# Power.net
KiCad netlist of a schematic drawn in Altium Designer
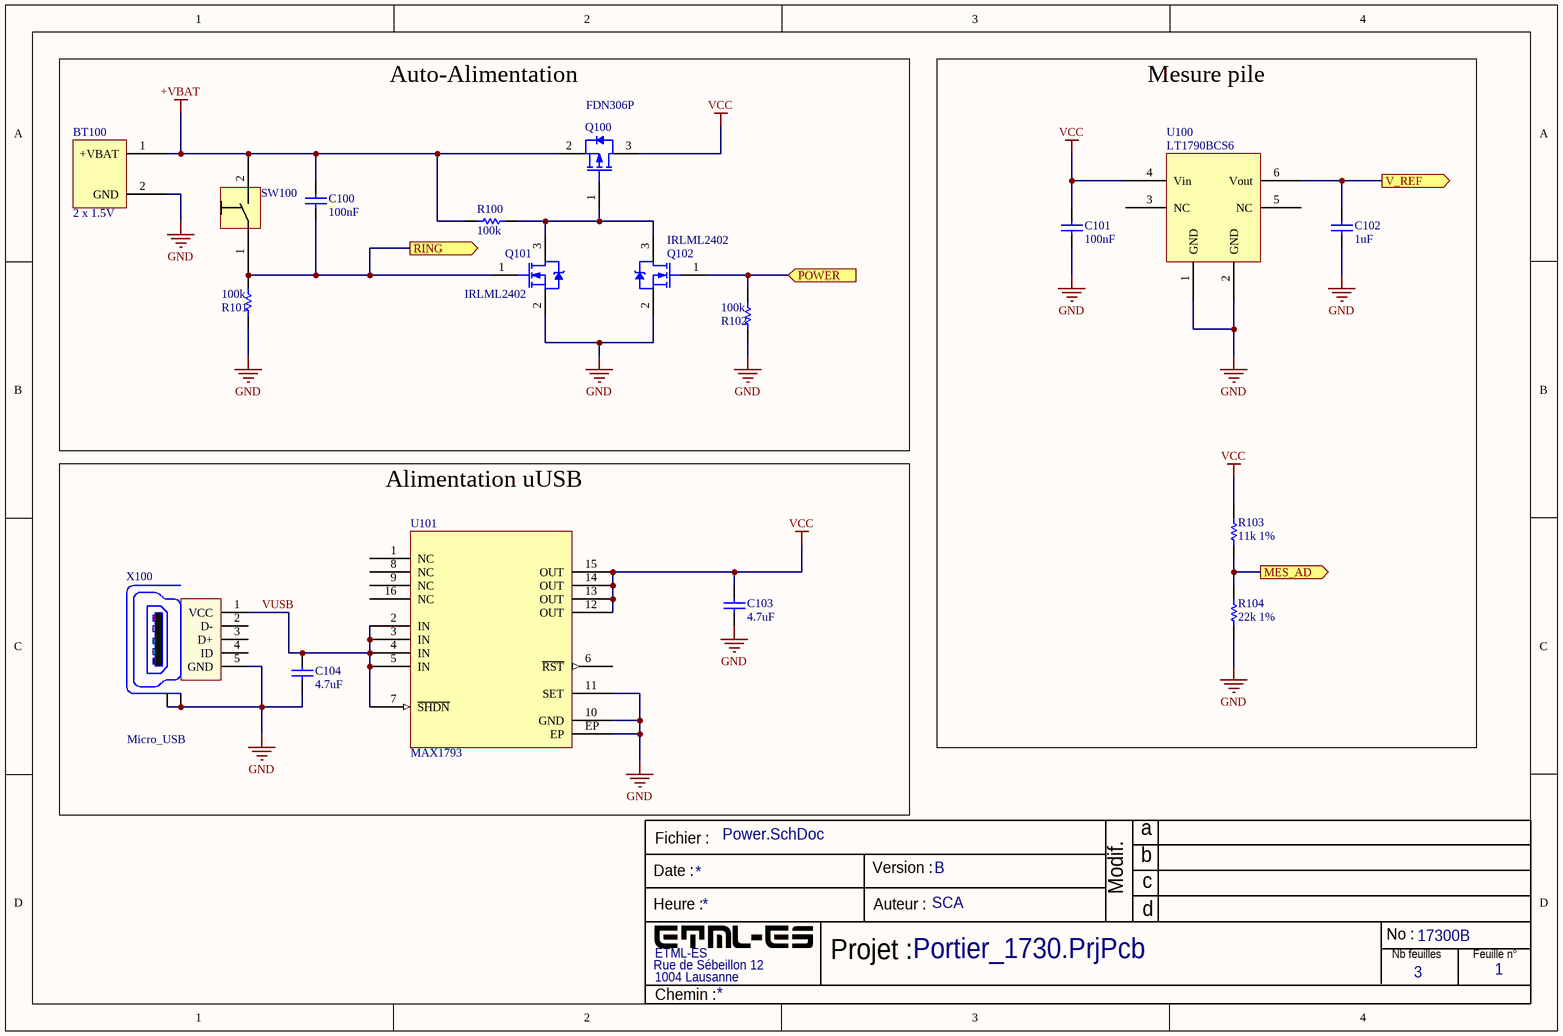
[diagram p0: Power.SchDoc]

(export (version "E")
  (design (tool "Eeschema 10.0.6"))
  (components
    (comp (ref "BT100")
      (value "2 x 1.5V")
      (footprint "BatterySupport")
      (description "Battery Support 2x1.5V type AAA")
      (libsource (lib "CircuitOUT") (part "Battery connector AAA"))
    )
    (comp (ref "C100")
      (value "100nF")
      (footprint "CAPC2013X100X20NL20")
      (description "Chip Capacitor, 100 nF, +/- 10%, 16 V, -55 to 85 degC, 0805 (2012 Metric), RoHS, Tape and Reel")
      (libsource (lib "Altium Content Vault") (part "CMP-1663-00007-1"))
    )
    (comp (ref "C101")
      (value "100nF")
      (footprint "CAPC2013X100X20NL20")
      (description "Chip Capacitor, 100 nF, +/- 10%, 16 V, -55 to 85 degC, 0805 (2012 Metric), RoHS, Tape and Reel")
      (libsource (lib "Altium Content Vault") (part "CMP-1663-00007-1"))
    )
    (comp (ref "C102")
      (value "1uF")
      (footprint "CAPC2013X145X50ML20T25")
      (description "Chip Capacitor, 1 uF, 25 V, 10%, -55 to 125 degC, 0805 (2012 Metric), RoHS, Tape and Reel")
      (libsource (lib "Altium Content Vault") (part "CMP-2100-03605-1"))
    )
    (comp (ref "C103")
      (value "4.7uF")
      (footprint "CAPC2013X135X45LL10T25")
      (description "Chip Capacitor, 4.7 uF, +/- 10%, 16 V, -55 to 85 degC, 0805 (2012 Metric), RoHS, Tape and Reel")
      (fields (field (name "PARTNUMBER") "GRM21BR61C475KA88L"))
      (libsource (lib "Altium Content Vault") (part "CMP-1662-00015-2"))
    )
    (comp (ref "C104")
      (value "4.7uF")
      (footprint "CAPC2013X135X45LL10T25")
      (description "Chip Capacitor, 4.7 uF, +/- 10%, 16 V, -55 to 85 degC, 0805 (2012 Metric), RoHS, Tape and Reel")
      (fields (field (name "PARTNUMBER") "GRM21BR61C475KA88L"))
      (libsource (lib "Altium Content Vault") (part "CMP-1662-00015-2"))
    )
    (comp (ref "Q100")
      (value "FDN306P")
      (footprint "FAIR-SSOT3L-3_V")
      (fields (field (name "MANUFACTURER") "ON Semiconductor"))
      (libsource (lib "Altium Content Vault") (part "CMP-2000-06248-1"))
    )
    (comp (ref "Q101")
      (value "IRLML2402")
      (footprint "INTR-IRLML2402TRPBF-3_V")
      (description "HEXFET(R) Power MOSFET, N-Channel, 20 V, 1.2 A, 3-Pin SOT-23, RoHS, Tape and Reel")
      (fields
        (field (name "MANUFACTURER") "Infineon Technologies")
        (field (name "PARTNUMBER") "IRLML2402TRBF")
      )
      (libsource (lib "Altium Content Vault") (part "CMP-2000-05155-1"))
    )
    (comp (ref "Q102")
      (value "IRLML2402")
      (footprint "INTR-IRLML2402TRPBF-3_V")
      (description "HEXFET(R) Power MOSFET, N-Channel, 20 V, 1.2 A, 3-Pin SOT-23, RoHS, Tape and Reel")
      (fields
        (field (name "MANUFACTURER") "Infineon Technologies")
        (field (name "PARTNUMBER") "IRLML2402TRBF")
      )
      (libsource (lib "Altium Content Vault") (part "CMP-2000-05155-1"))
    )
    (comp (ref "R100")
      (value "100k")
      (footprint "RESC2013X60X35ML10T20")
      (description "Chip Resistor, 100 KOhm, +/- 1%, 125 mW, -55 to 155 degC, 0805 (2012 Metric), RoHS, Tape and Reel")
      (libsource (lib "Altium Content Vault") (part "CMP-2100-03671-1"))
    )
    (comp (ref "R101")
      (value "100k")
      (footprint "RESC2013X60X35ML10T20")
      (description "Chip Resistor, 100 KOhm, +/- 1%, 125 mW, -55 to 155 degC, 0805 (2012 Metric), RoHS, Tape and Reel")
      (libsource (lib "Altium Content Vault") (part "CMP-2100-03671-1"))
    )
    (comp (ref "R102")
      (value "100k")
      (footprint "RESC2013X60X35ML10T20")
      (description "Chip Resistor, 100 KOhm, +/- 1%, 125 mW, -55 to 155 degC, 0805 (2012 Metric), RoHS, Tape and Reel")
      (libsource (lib "Altium Content Vault") (part "CMP-2100-03671-1"))
    )
    (comp (ref "R103")
      (value "11k 1%")
      (footprint "RESC0805(2012)_N")
      (description "11k 0.125W 0805 (2012 Metric)  SMD")
      (libsource (lib "Altium Content Vault") (part "CMP-1013-00075-1"))
    )
    (comp (ref "R104")
      (value "22k 1%")
      (footprint "RESC0805(2012)_L")
      (description "22k 0.125W  0805 (2012 Metric)  SMD")
      (libsource (lib "Altium Content Vault") (part "CMP-1013-00082-1"))
    )
    (comp (ref "SW100")
      (value "Poussoir")
      (footprint "Switch_Schurter")
      (description "Switch 12.7x12.7x17.5")
      (fields (field (name "MANUFACTURER") "Schurter"))
      (libsource (lib "CircuitOUT") (part "Switch_Schurter"))
    )
    (comp (ref "U100")
      (value "LT1790BCS6")
      (footprint "SOT-23")
      (description "IC VREF SERIES 2.048V SOT23-6")
      (fields
        (field (name "MANUFACTURER") "Linear Technology")
        (field (name "PARTNUMBER") "LT1790BCS6-2.048#TRMPBF")
      )
      (libsource (lib "CircuitOUT") (part "LT1790"))
    )
    (comp (ref "U101")
      (value "MAX1793")
      (footprint "TSOP65P640X110_HS-17N")
      (description "IC REG LINEAR POS ADJ 1A 16TSSOP")
      (fields (field (name "MANUFACTURER") "Maxim Integrated"))
      (libsource (lib "CircuitOUT") (part "MAX1793"))
    )
    (comp (ref "X100")
      (value "Micro_USB")
      (footprint "Micro_USB")
      (description "WR-COM_USB_Micro Type B_Horizontal_SMT")
      (fields
        (field (name "MANUFACTURER") "Würth Elektronik eiSos GmbH")
        (field (name "PARTNUMBER") "629105150521")
      )
      (libsource (lib "CircuitOUT") (part "WR-Communication Connectors 629105150521"))
    )
  )
  (nets
    (net (code "1") (name "+VBAT") (class "Default")
      (node (ref "BT100") (pin "1") (pinfunction "+VBAT_1") (pintype "power_in"))
      (node (ref "C100") (pin "2") (pinfunction "2_2") (pintype "passive"))
      (node (ref "Q100") (pin "2") (pinfunction "SOURCE_2") (pintype "passive"))
      (node (ref "R100") (pin "2") (pinfunction "2_2") (pintype "passive"))
      (node (ref "SW100") (pin "2") (pinfunction "2_2") (pintype "passive"))
    )
    (net (code "2") (name "/MES_AD") (class "Default")
      (node (ref "R103") (pin "1") (pinfunction "1_1") (pintype "passive"))
      (node (ref "R104") (pin "2") (pinfunction "2_2") (pintype "passive"))
    )
    (net (code "3") (name "/POWER") (class "Default")
      (node (ref "Q102") (pin "1") (pinfunction "G_1") (pintype "passive"))
      (node (ref "R102") (pin "2") (pinfunction "2_2") (pintype "passive"))
    )
    (net (code "4") (name "/RING") (class "Default")
      (node (ref "C100") (pin "1") (pinfunction "1_1") (pintype "passive"))
      (node (ref "Q101") (pin "1") (pinfunction "G_1") (pintype "passive"))
      (node (ref "R101") (pin "2") (pinfunction "2_2") (pintype "passive"))
      (node (ref "SW100") (pin "1") (pinfunction "1_1") (pintype "passive"))
    )
    (net (code "5") (name "/VUSB") (class "Default")
      (node (ref "C104") (pin "2") (pinfunction "2_2") (pintype "passive"))
      (node (ref "U101") (pin "2") (pinfunction "IN_2") (pintype "passive"))
      (node (ref "U101") (pin "3") (pinfunction "IN_3") (pintype "passive"))
      (node (ref "U101") (pin "4") (pinfunction "IN_4") (pintype "passive"))
      (node (ref "U101") (pin "5") (pinfunction "IN_5") (pintype "passive"))
      (node (ref "U101") (pin "7") (pinfunction "~{SHDN}_7") (pintype "input"))
      (node (ref "X100") (pin "1") (pinfunction "VCC_1") (pintype "passive"))
    )
    (net (code "6") (name "/V_REF") (class "Default")
      (node (ref "C102") (pin "2") (pinfunction "2_2") (pintype "passive"))
      (node (ref "U100") (pin "6") (pinfunction "Vout_6") (pintype "passive"))
    )
    (net (code "7") (name "GND") (class "Default")
      (node (ref "BT100") (pin "2") (pinfunction "GND_2") (pintype "power_in"))
      (node (ref "C101") (pin "1") (pinfunction "1_1") (pintype "passive"))
      (node (ref "C102") (pin "1") (pinfunction "1_1") (pintype "passive"))
      (node (ref "C103") (pin "1") (pinfunction "1_1") (pintype "passive"))
      (node (ref "C104") (pin "1") (pinfunction "1_1") (pintype "passive"))
      (node (ref "Q101") (pin "2") (pinfunction "S_2") (pintype "passive"))
      (node (ref "Q102") (pin "2") (pinfunction "S_2") (pintype "passive"))
      (node (ref "R101") (pin "1") (pinfunction "1_1") (pintype "passive"))
      (node (ref "R102") (pin "1") (pinfunction "1_1") (pintype "passive"))
      (node (ref "R104") (pin "1") (pinfunction "1_1") (pintype "passive"))
      (node (ref "U100") (pin "1") (pinfunction "GND_1") (pintype "passive"))
      (node (ref "U100") (pin "2") (pinfunction "GND_2") (pintype "passive"))
      (node (ref "U101") (pin "10") (pinfunction "GND_10") (pintype "passive"))
      (node (ref "U101") (pin "11") (pinfunction "SET_11") (pintype "passive"))
      (node (ref "U101") (pin "EP") (pinfunction "EP_EP") (pintype "passive"))
      (node (ref "X100") (pin "5") (pinfunction "GND_5") (pintype "passive"))
      (node (ref "X100") (pin "Z1") (pinfunction "Shield_Z1") (pintype "passive"))
      (node (ref "X100") (pin "Z2") (pinfunction "Shield_Z2") (pintype "passive"))
    )
    (net (code "8") (name "Net-(Q100-GATE)") (class "Default")
      (node (ref "Q100") (pin "1") (pinfunction "GATE_1") (pintype "passive"))
      (node (ref "Q101") (pin "3") (pinfunction "D_3") (pintype "passive"))
      (node (ref "Q102") (pin "3") (pinfunction "D_3") (pintype "passive"))
      (node (ref "R100") (pin "1") (pinfunction "1_1") (pintype "passive"))
    )
    (net (code "9") (name "VCC") (class "Default")
      (node (ref "C101") (pin "2") (pinfunction "2_2") (pintype "passive"))
      (node (ref "C103") (pin "2") (pinfunction "2_2") (pintype "passive"))
      (node (ref "Q100") (pin "3") (pinfunction "DRAIN_3") (pintype "passive"))
      (node (ref "R103") (pin "2") (pinfunction "2_2") (pintype "passive"))
      (node (ref "U100") (pin "4") (pinfunction "Vin_4") (pintype "passive"))
      (node (ref "U101") (pin "12") (pinfunction "OUT_12") (pintype "passive"))
      (node (ref "U101") (pin "13") (pinfunction "OUT_13") (pintype "passive"))
      (node (ref "U101") (pin "14") (pinfunction "OUT_14") (pintype "passive"))
      (node (ref "U101") (pin "15") (pinfunction "OUT_15") (pintype "passive"))
    )
    (net (code "10") (name "unconnected-(U100-NC-Pad3)") (class "Default")
      (node (ref "U100") (pin "3") (pinfunction "NC_3") (pintype "passive"))
    )
    (net (code "11") (name "unconnected-(U100-NC-Pad5)") (class "Default")
      (node (ref "U100") (pin "5") (pinfunction "NC_5") (pintype "passive"))
    )
    (net (code "12") (name "unconnected-(U101-NC-Pad1)") (class "Default")
      (node (ref "U101") (pin "1") (pinfunction "NC_1") (pintype "passive"))
    )
    (net (code "13") (name "unconnected-(U101-NC-Pad8)") (class "Default")
      (node (ref "U101") (pin "8") (pinfunction "NC_8") (pintype "passive"))
    )
    (net (code "14") (name "unconnected-(U101-NC-Pad9)") (class "Default")
      (node (ref "U101") (pin "9") (pinfunction "NC_9") (pintype "passive"))
    )
    (net (code "15") (name "unconnected-(U101-NC-Pad16)") (class "Default")
      (node (ref "U101") (pin "16") (pinfunction "NC_16") (pintype "passive"))
    )
    (net (code "16") (name "unconnected-(U101-~{RST}-Pad6)") (class "Default")
      (node (ref "U101") (pin "6") (pinfunction "~{RST}_6") (pintype "output"))
    )
    (net (code "17") (name "unconnected-(X100-D+-Pad3)") (class "Default")
      (node (ref "X100") (pin "3") (pinfunction "D+_3") (pintype "passive"))
    )
    (net (code "18") (name "unconnected-(X100-D--Pad2)") (class "Default")
      (node (ref "X100") (pin "2") (pinfunction "D-_2") (pintype "passive"))
    )
    (net (code "19") (name "unconnected-(X100-ID-Pad4)") (class "Default")
      (node (ref "X100") (pin "4") (pinfunction "ID_4") (pintype "passive"))
    )
  )
)
